# SR-26424.net
KiCad netlist of a schematic drawn in Altium Designer
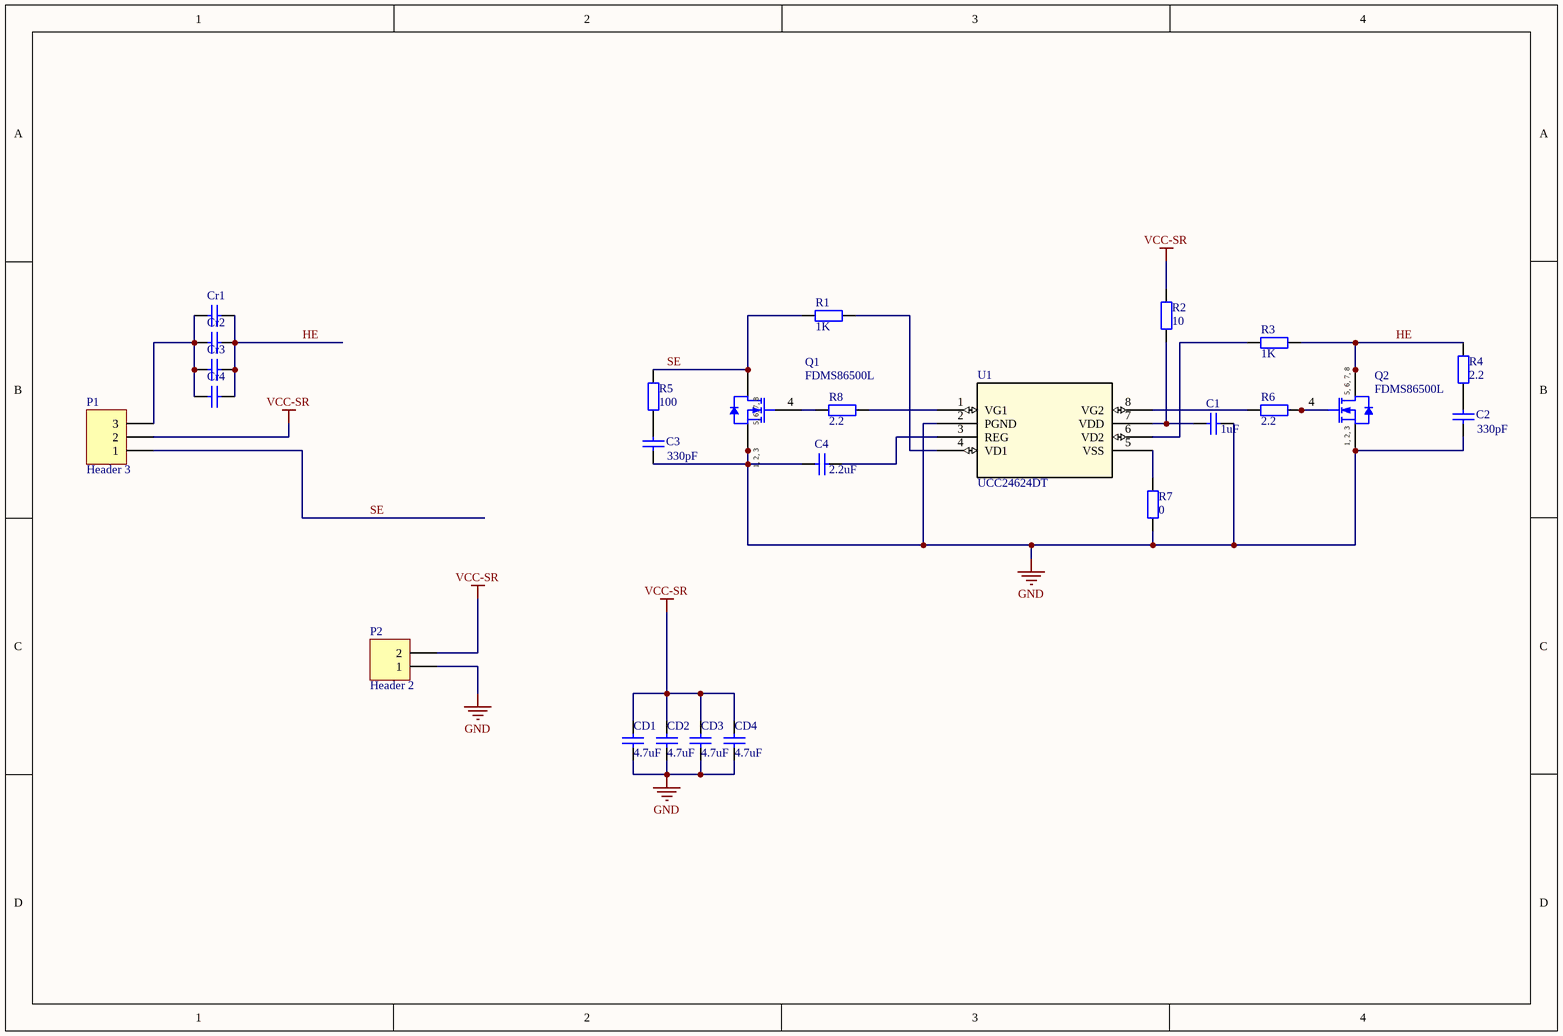
[diagram p0: SR-26424.SchDoc]

(export (version "E")
  (design (tool "Eeschema 10.0.6"))
  (components
    (comp (ref "C1")
      (value "1uF")
      (footprint "C0603")
      (description "Capacitor")
      (fields (field (name "Comment") "Cap") (field (name "PUBLISHER") "Altium Limited"))
      (libsource (lib "Miscellaneous Devices") (part "Cap"))
    )
    (comp (ref "C2")
      (value "330pF")
      (footprint "0603-C")
      (description "Capacitor")
      (fields (field (name "Comment") "Cap") (field (name "PUBLISHER") "Altium Limited"))
      (libsource (lib "Miscellaneous Devices") (part "Cap"))
    )
    (comp (ref "C3")
      (value "330pF")
      (footprint "0603-C")
      (description "Capacitor")
      (fields (field (name "Comment") "Cap") (field (name "PUBLISHER") "Altium Limited"))
      (libsource (lib "Miscellaneous Devices") (part "Cap"))
    )
    (comp (ref "C4")
      (value "2.2uF")
      (footprint "C0603")
      (description "Capacitor")
      (fields (field (name "Comment") "Cap") (field (name "PUBLISHER") "Altium Limited"))
      (libsource (lib "Miscellaneous Devices") (part "Cap"))
    )
    (comp (ref "CD1")
      (value "4.7uF")
      (footprint "0603-C")
      (description "Capacitor")
      (fields (field (name "Comment") "Cap") (field (name "PUBLISHER") "Altium Limited"))
      (libsource (lib "Miscellaneous Devices") (part "Cap"))
    )
    (comp (ref "CD2")
      (value "4.7uF")
      (footprint "0603-C")
      (description "Capacitor")
      (fields (field (name "Comment") "Cap") (field (name "PUBLISHER") "Altium Limited"))
      (libsource (lib "Miscellaneous Devices") (part "Cap"))
    )
    (comp (ref "CD3")
      (value "4.7uF")
      (footprint "0603-C")
      (description "Capacitor")
      (fields (field (name "Comment") "Cap") (field (name "PUBLISHER") "Altium Limited"))
      (libsource (lib "Miscellaneous Devices") (part "Cap"))
    )
    (comp (ref "CD4")
      (value "4.7uF")
      (footprint "0603-C")
      (description "Capacitor")
      (fields (field (name "Comment") "Cap") (field (name "PUBLISHER") "Altium Limited"))
      (libsource (lib "Miscellaneous Devices") (part "Cap"))
    )
    (comp (ref "Cr1")
      (value "Cap")
      (footprint "C0805")
      (description "Capacitor")
      (fields (field (name "PUBLISHER") "Altium Limited"))
      (libsource (lib "Miscellaneous Devices") (part "Cap"))
    )
    (comp (ref "Cr2")
      (value "Cap")
      (footprint "C0805")
      (description "Capacitor")
      (fields (field (name "PUBLISHER") "Altium Limited"))
      (libsource (lib "Miscellaneous Devices") (part "Cap"))
    )
    (comp (ref "Cr3")
      (value "Cap")
      (footprint "C0805")
      (description "Capacitor")
      (fields (field (name "PUBLISHER") "Altium Limited"))
      (libsource (lib "Miscellaneous Devices") (part "Cap"))
    )
    (comp (ref "Cr4")
      (value "Cap")
      (footprint "C0805")
      (description "Capacitor")
      (fields (field (name "PUBLISHER") "Altium Limited"))
      (libsource (lib "Miscellaneous Devices") (part "Cap"))
    )
    (comp (ref "P1")
      (value "Header 3")
      (footprint "3PIN-5.08B")
      (description "Header, 3-Pin")
      (fields (field (name "PUBLISHER") "Altium Limited"))
      (libsource (lib "Miscellaneous Connectors") (part "Header 3"))
    )
    (comp (ref "P2")
      (value "Header 2")
      (footprint "2PIN-5.08B")
      (description "Header, 2-Pin")
      (fields (field (name "PUBLISHER") "Altium Limited"))
      (libsource (lib "Miscellaneous Connectors") (part "Header 2"))
    )
    (comp (ref "Q1")
      (value "FDMS86500L")
      (footprint "INF-PG-TDSON-8-1_V")
      (description "N-Channel OptiMOS 3 Power-Transistor, 150燰 VDS, 50燗 ID, -55 to 150 degC, PG-TDSON-8-1, Reel, Green")
      (fields (field (name "MANUFACTURER") "Infineon") (field (name "PARTNUMBER") "BSC190N15NS3 G"))
      (libsource (lib "BSC190N15NS3 G") (part "BSC190N15NS3 G"))
    )
    (comp (ref "Q2")
      (value "FDMS86500L")
      (footprint "INF-PG-TDSON-8-1_V")
      (description "N-Channel OptiMOS 3 Power-Transistor, 150燰 VDS, 50燗 ID, -55 to 150 degC, PG-TDSON-8-1, Reel, Green")
      (fields (field (name "MANUFACTURER") "Infineon") (field (name "PARTNUMBER") "BSC190N15NS3 G"))
      (libsource (lib "BSC190N15NS3 G") (part "BSC190N15NS3 G"))
    )
    (comp (ref "R1")
      (value "1K")
      (footprint "R0603")
      (description "Resistor")
      (fields (field (name "Comment") "Res2") (field (name "PUBLISHER") "Altium Limited"))
      (libsource (lib "Miscellaneous Devices") (part "Res2"))
    )
    (comp (ref "R2")
      (value "10")
      (footprint "R0603")
      (description "Resistor")
      (fields (field (name "Comment") "Res2") (field (name "PUBLISHER") "Altium Limited"))
      (libsource (lib "") (part "Res2_1"))
    )
    (comp (ref "R3")
      (value "1K")
      (footprint "R0603")
      (description "Resistor")
      (fields (field (name "Comment") "Res2") (field (name "PUBLISHER") "Altium Limited"))
      (libsource (lib "Miscellaneous Devices") (part "Res2"))
    )
    (comp (ref "R4")
      (value "2.2")
      (footprint "R0603")
      (description "Resistor")
      (fields (field (name "Comment") "Res2") (field (name "PUBLISHER") "Altium Limited"))
      (libsource (lib "") (part "Res2_2"))
    )
    (comp (ref "R5")
      (value "100")
      (footprint "R0603")
      (description "Resistor")
      (fields (field (name "Comment") "Res2") (field (name "PUBLISHER") "Altium Limited"))
      (libsource (lib "") (part "Res2_2"))
    )
    (comp (ref "R6")
      (value "2.2")
      (footprint "R0603")
      (description "Resistor")
      (fields (field (name "Comment") "Res2") (field (name "PUBLISHER") "Altium Limited"))
      (libsource (lib "Miscellaneous Devices") (part "Res2"))
    )
    (comp (ref "R7")
      (value "0")
      (footprint "R0603")
      (description "Resistor")
      (fields (field (name "Comment") "Res2") (field (name "PUBLISHER") "Altium Limited"))
      (libsource (lib "") (part "Res2_2"))
    )
    (comp (ref "R8")
      (value "2.2")
      (footprint "R0603")
      (description "Resistor")
      (fields (field (name "Comment") "Res2") (field (name "PUBLISHER") "Altium Limited"))
      (libsource (lib "") (part "Res2_1"))
    )
    (comp (ref "U1")
      (value "UCC24624DT")
      (footprint "SOIC_4624DT_TEX")
      (description "No Description Available")
      (fields (field (name "COPYRIGHT") "Copyright (C) 2018 Accelerated Designs. All rights reserved"))
      (libsource (lib "UCC24624") (part "UCC24624DT"))
    )
  )
  (nets
    (net (code "1") (name "/HE") (class "Default")
      (node (ref "Cr1") (pin "2") (pinfunction "2_2") (pintype "passive"))
      (node (ref "Cr2") (pin "2") (pinfunction "2_2") (pintype "passive"))
      (node (ref "Cr3") (pin "2") (pinfunction "2_2") (pintype "passive"))
      (node (ref "Cr4") (pin "2") (pinfunction "2_2") (pintype "passive"))
      (node (ref "Q2") (pin "5") (pinfunction "DRAIN_5") (pintype "passive"))
      (node (ref "Q2") (pin "6") (pinfunction "DRAIN_6") (pintype "passive"))
      (node (ref "Q2") (pin "7") (pinfunction "DRAIN_7") (pintype "passive"))
      (node (ref "Q2") (pin "8") (pinfunction "DRAIN_8") (pintype "passive"))
      (node (ref "R3") (pin "1") (pinfunction "1_1") (pintype "passive"))
      (node (ref "R4") (pin "2") (pinfunction "2_2") (pintype "passive"))
    )
    (net (code "2") (name "/SE") (class "Default")
      (node (ref "P1") (pin "1") (pinfunction "1_1") (pintype "passive"))
      (node (ref "Q1") (pin "5") (pinfunction "DRAIN_5") (pintype "passive"))
      (node (ref "Q1") (pin "6") (pinfunction "DRAIN_6") (pintype "passive"))
      (node (ref "Q1") (pin "7") (pinfunction "DRAIN_7") (pintype "passive"))
      (node (ref "Q1") (pin "8") (pinfunction "DRAIN_8") (pintype "passive"))
      (node (ref "R1") (pin "2") (pinfunction "2_2") (pintype "passive"))
      (node (ref "R5") (pin "2") (pinfunction "2_2") (pintype "passive"))
    )
    (net (code "3") (name "GND") (class "Default")
      (node (ref "C1") (pin "1") (pinfunction "1_1") (pintype "passive"))
      (node (ref "C2") (pin "1") (pinfunction "1_1") (pintype "passive"))
      (node (ref "C3") (pin "1") (pinfunction "1_1") (pintype "passive"))
      (node (ref "C4") (pin "2") (pinfunction "2_2") (pintype "passive"))
      (node (ref "CD1") (pin "1") (pinfunction "1_1") (pintype "passive"))
      (node (ref "CD2") (pin "1") (pinfunction "1_1") (pintype "passive"))
      (node (ref "CD3") (pin "1") (pinfunction "1_1") (pintype "passive"))
      (node (ref "CD4") (pin "1") (pinfunction "1_1") (pintype "passive"))
      (node (ref "P2") (pin "1") (pinfunction "1_1") (pintype "passive"))
      (node (ref "Q1") (pin "1") (pinfunction "SOURCE_1") (pintype "passive"))
      (node (ref "Q1") (pin "2") (pinfunction "SOURCE_2") (pintype "passive"))
      (node (ref "Q1") (pin "3") (pinfunction "SOURCE_3") (pintype "passive"))
      (node (ref "Q2") (pin "1") (pinfunction "SOURCE_1") (pintype "passive"))
      (node (ref "Q2") (pin "2") (pinfunction "SOURCE_2") (pintype "passive"))
      (node (ref "Q2") (pin "3") (pinfunction "SOURCE_3") (pintype "passive"))
      (node (ref "R7") (pin "1") (pinfunction "1_1") (pintype "passive"))
      (node (ref "U1") (pin "2") (pinfunction "PGND_2") (pintype "passive"))
    )
    (net (code "4") (name "Net-(C2-Pad2)") (class "Default")
      (node (ref "C2") (pin "2") (pinfunction "2_2") (pintype "passive"))
      (node (ref "R4") (pin "1") (pinfunction "1_1") (pintype "passive"))
    )
    (net (code "5") (name "Net-(C3-Pad2)") (class "Default")
      (node (ref "C3") (pin "2") (pinfunction "2_2") (pintype "passive"))
      (node (ref "R5") (pin "1") (pinfunction "1_1") (pintype "passive"))
    )
    (net (code "6") (name "Net-(Cr1-Pad1)") (class "Default")
      (node (ref "Cr1") (pin "1") (pinfunction "1_1") (pintype "passive"))
      (node (ref "Cr2") (pin "1") (pinfunction "1_1") (pintype "passive"))
      (node (ref "Cr3") (pin "1") (pinfunction "1_1") (pintype "passive"))
      (node (ref "Cr4") (pin "1") (pinfunction "1_1") (pintype "passive"))
      (node (ref "P1") (pin "3") (pinfunction "3_3") (pintype "passive"))
    )
    (net (code "7") (name "Net-(Q1-GATE)") (class "Default")
      (node (ref "Q1") (pin "4") (pinfunction "GATE_4") (pintype "passive"))
      (node (ref "R8") (pin "2") (pinfunction "2_2") (pintype "passive"))
    )
    (net (code "8") (name "Net-(Q2-GATE)") (class "Default")
      (node (ref "Q2") (pin "4") (pinfunction "GATE_4") (pintype "passive"))
      (node (ref "R6") (pin "1") (pinfunction "1_1") (pintype "passive"))
    )
    (net (code "9") (name "Net-(U1-REG)") (class "Default")
      (node (ref "C4") (pin "1") (pinfunction "1_1") (pintype "passive"))
      (node (ref "U1") (pin "3") (pinfunction "REG_3") (pintype "passive"))
    )
    (net (code "10") (name "Net-(U1-VD1)") (class "Default")
      (node (ref "R1") (pin "1") (pinfunction "1_1") (pintype "passive"))
      (node (ref "U1") (pin "4") (pinfunction "VD1_4") (pintype "bidirectional"))
    )
    (net (code "11") (name "Net-(U1-VD2)") (class "Default")
      (node (ref "R3") (pin "2") (pinfunction "2_2") (pintype "passive"))
      (node (ref "U1") (pin "6") (pinfunction "VD2_6") (pintype "bidirectional"))
    )
    (net (code "12") (name "Net-(U1-VDD)") (class "Default")
      (node (ref "C1") (pin "2") (pinfunction "2_2") (pintype "passive"))
      (node (ref "R2") (pin "2") (pinfunction "2_2") (pintype "passive"))
      (node (ref "U1") (pin "7") (pinfunction "VDD_7") (pintype "power_in"))
    )
    (net (code "13") (name "Net-(U1-VG1)") (class "Default")
      (node (ref "R8") (pin "1") (pinfunction "1_1") (pintype "passive"))
      (node (ref "U1") (pin "1") (pinfunction "VG1_1") (pintype "bidirectional"))
    )
    (net (code "14") (name "Net-(U1-VG2)") (class "Default")
      (node (ref "R6") (pin "2") (pinfunction "2_2") (pintype "passive"))
      (node (ref "U1") (pin "8") (pinfunction "VG2_8") (pintype "bidirectional"))
    )
    (net (code "15") (name "Net-(U1-VSS)") (class "Default")
      (node (ref "R7") (pin "2") (pinfunction "2_2") (pintype "passive"))
      (node (ref "U1") (pin "5") (pinfunction "VSS_5") (pintype "passive"))
    )
    (net (code "16") (name "VCC-SR") (class "Default")
      (node (ref "CD1") (pin "2") (pinfunction "2_2") (pintype "passive"))
      (node (ref "CD2") (pin "2") (pinfunction "2_2") (pintype "passive"))
      (node (ref "CD3") (pin "2") (pinfunction "2_2") (pintype "passive"))
      (node (ref "CD4") (pin "2") (pinfunction "2_2") (pintype "passive"))
      (node (ref "P1") (pin "2") (pinfunction "2_2") (pintype "passive"))
      (node (ref "P2") (pin "2") (pinfunction "2_2") (pintype "passive"))
      (node (ref "R2") (pin "1") (pinfunction "1_1") (pintype "passive"))
    )
  )
)
